# Sheet3.net
KiCad netlist of a schematic drawn in Altium Designer
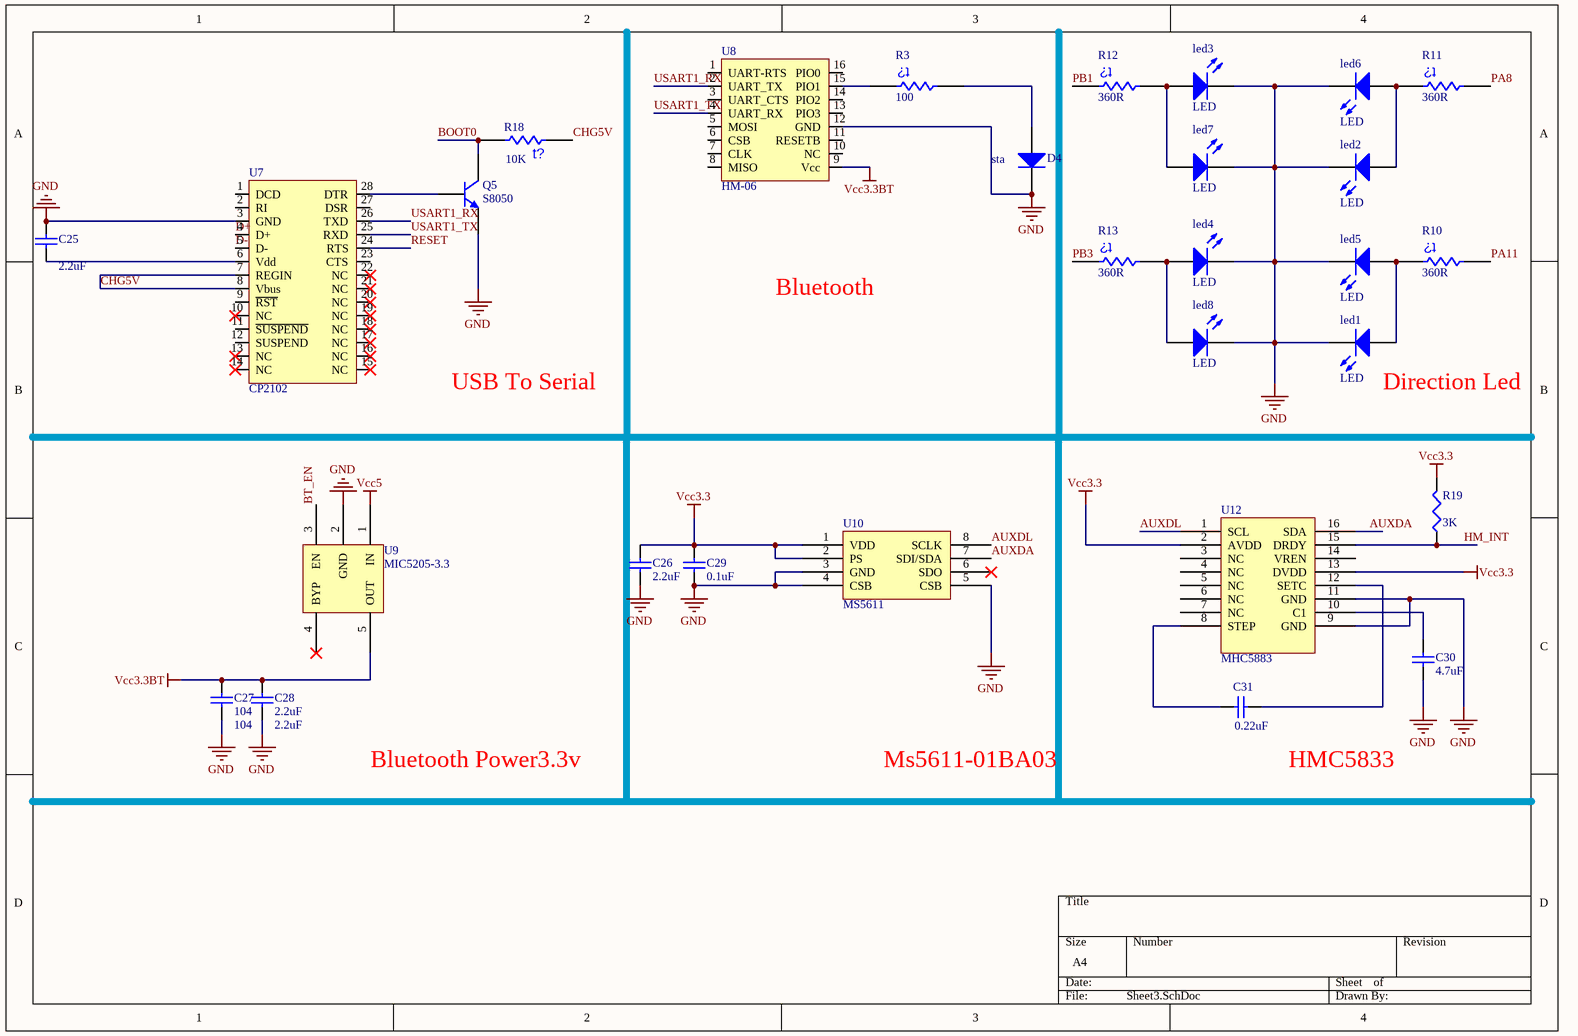
[diagram p0: Sheet3.SchDoc]

(export (version "E")
  (design (tool "Eeschema 10.0.6"))
  (components
    (comp (ref "C25")
      (value "2.2uF")
      (footprint "1608[0603]")
      (description "Capacitor (Semiconductor SIM Model)")
      (fields (field (name "PUBLISHER") "Altium Limited"))
      (libsource (lib "Miscellaneous Devices") (part "Cap Semi"))
    )
    (comp (ref "C26")
      (value "2.2uF")
      (footprint "1608[0603]")
      (description "Capacitor (Semiconductor SIM Model)")
      (fields (field (name "PUBLISHER") "Altium Limited"))
      (libsource (lib "Miscellaneous Devices") (part "Cap Semi"))
    )
    (comp (ref "C27")
      (value "104")
      (footprint "1608[0603]")
      (description "Capacitor (Semiconductor SIM Model)")
      (fields (field (name "ALTIUM_VALUE") "104") (field (name "PUBLISHER") "Altium Limited"))
      (libsource (lib "Miscellaneous Devices") (part "Cap Semi"))
    )
    (comp (ref "C28")
      (value "2.2uF")
      (footprint "1608[0603]")
      (description "Capacitor (Semiconductor SIM Model)")
      (fields (field (name "ALTIUM_VALUE") "2.2uF") (field (name "PUBLISHER") "Altium Limited"))
      (libsource (lib "Miscellaneous Devices") (part "Cap Semi"))
    )
    (comp (ref "C29")
      (value "0.1uF")
      (footprint "1608[0603]")
      (description "Capacitor (Semiconductor SIM Model)")
      (fields (field (name "PUBLISHER") "Altium Limited"))
      (libsource (lib "Miscellaneous Devices") (part "Cap Semi"))
    )
    (comp (ref "C30")
      (value "4.7uF")
      (footprint "1608[0603]")
      (description "Capacitor (Semiconductor SIM Model)")
      (fields (field (name "PUBLISHER") "Altium Limited"))
      (libsource (lib "Miscellaneous Devices") (part "Cap Semi"))
    )
    (comp (ref "C31")
      (value "0.22uF")
      (footprint "1608[0603]")
      (description "Capacitor (Semiconductor SIM Model)")
      (fields (field (name "PUBLISHER") "Altium Limited"))
      (libsource (lib "Miscellaneous Devices") (part "Cap Semi"))
    )
    (comp (ref "D4")
      (value "sta")
      (footprint "6-0805_N")
      (description "Default Diode")
      (fields (field (name "PUBLISHER") "Altium Limited"))
      (libsource (lib "Miscellaneous Devices") (part "Diode"))
    )
    (comp (ref "led1")
      (value "LED")
      (footprint "6-0805_N")
      (description "Typical RED, GREEN, YELLOW, AMBER GaAs LED")
      (fields (field (name "PUBLISHER") "Altium Limited"))
      (libsource (lib "Miscellaneous Devices") (part "LED2"))
    )
    (comp (ref "led2")
      (value "LED")
      (footprint "6-0805_N")
      (description "Typical RED, GREEN, YELLOW, AMBER GaAs LED")
      (fields (field (name "PUBLISHER") "Altium Limited"))
      (libsource (lib "Miscellaneous Devices") (part "LED2"))
    )
    (comp (ref "led3")
      (value "LED")
      (footprint "6-0805_N")
      (description "Typical RED, GREEN, YELLOW, AMBER GaAs LED")
      (fields (field (name "PUBLISHER") "Altium Limited"))
      (libsource (lib "Miscellaneous Devices") (part "LED2"))
    )
    (comp (ref "led4")
      (value "LED")
      (footprint "6-0805_N")
      (description "Typical RED, GREEN, YELLOW, AMBER GaAs LED")
      (fields (field (name "PUBLISHER") "Altium Limited"))
      (libsource (lib "Miscellaneous Devices") (part "LED2"))
    )
    (comp (ref "led5")
      (value "LED")
      (footprint "6-0805_N")
      (description "Typical RED, GREEN, YELLOW, AMBER GaAs LED")
      (fields (field (name "PUBLISHER") "Altium Limited"))
      (libsource (lib "Miscellaneous Devices") (part "LED2"))
    )
    (comp (ref "led6")
      (value "LED")
      (footprint "6-0805_N")
      (description "Typical RED, GREEN, YELLOW, AMBER GaAs LED")
      (fields (field (name "PUBLISHER") "Altium Limited"))
      (libsource (lib "Miscellaneous Devices") (part "LED2"))
    )
    (comp (ref "led7")
      (value "LED")
      (footprint "6-0805_N")
      (description "Typical RED, GREEN, YELLOW, AMBER GaAs LED")
      (fields (field (name "PUBLISHER") "Altium Limited"))
      (libsource (lib "Miscellaneous Devices") (part "LED2"))
    )
    (comp (ref "led8")
      (value "LED")
      (footprint "6-0805_N")
      (description "Typical RED, GREEN, YELLOW, AMBER GaAs LED")
      (fields (field (name "PUBLISHER") "Altium Limited"))
      (libsource (lib "Miscellaneous Devices") (part "LED2"))
    )
    (comp (ref "Q5")
      (value "S8050")
      (footprint "SOT-23B_N")
      (description "NPN Bipolar Transistor")
      (fields (field (name "PUBLISHER") "Altium Limited"))
      (libsource (lib "Miscellaneous Devices") (part "QNPN"))
    )
    (comp (ref "R3")
      (value "100")
      (footprint "6-0805_N")
      (fields (field (name "PUBLISHER") "Altium Limited"))
      (libsource (lib "Miscellaneous Devices") (part "Res Thermal"))
    )
    (comp (ref "R10")
      (value "360R")
      (footprint "6-0805_N")
      (fields (field (name "PUBLISHER") "Altium Limited"))
      (libsource (lib "Miscellaneous Devices") (part "Res Thermal"))
    )
    (comp (ref "R11")
      (value "360R")
      (footprint "6-0805_N")
      (fields (field (name "PUBLISHER") "Altium Limited"))
      (libsource (lib "Miscellaneous Devices") (part "Res Thermal"))
    )
    (comp (ref "R12")
      (value "360R")
      (footprint "6-0805_N")
      (fields (field (name "PUBLISHER") "Altium Limited"))
      (libsource (lib "Miscellaneous Devices") (part "Res Thermal"))
    )
    (comp (ref "R13")
      (value "360R")
      (footprint "6-0805_N")
      (fields (field (name "PUBLISHER") "Altium Limited"))
      (libsource (lib "Miscellaneous Devices") (part "Res Thermal"))
    )
    (comp (ref "R18")
      (value "10K")
      (footprint "6-0805_N")
      (fields (field (name "PUBLISHER") "Altium Limited"))
      (libsource (lib "Miscellaneous Devices") (part "Res Thermal"))
    )
    (comp (ref "R19")
      (value "3K")
      (footprint "0805")
      (description "Resistor")
      (fields (field (name "PUBLISHER") "Altium Limited"))
      (libsource (lib "Miscellaneous Devices") (part "Res3"))
    )
    (comp (ref "U7") (value "CP2102") (footprint "cp2102") (libsource (lib "stm32") (part "CP2102")))
    (comp (ref "U8") (value "HM-06") (footprint "HM-11") (libsource (lib "stm32") (part "bluetooth")))
    (comp (ref "U9")
      (value "MIC5205-3.3")
      (footprint "SOT95P280X120-5N")
      (libsource (lib "stm32") (part "MIC5205-3.3"))
    )
    (comp (ref "U10")
      (value "MS5611")
      (footprint "U6 - duplicate1")
      (libsource (lib "Ms5611") (part "Component_1"))
    )
    (comp (ref "U12")
      (value "HMC5833")
      (footprint "QFN50P302X302X90-16N")
      (libsource (lib "HMC5883") (part "Component_1"))
    )
  )
  (nets
    (net (code "1") (name "/AUXDA") (class "Default")
      (node (ref "U10") (pin "7") (pinfunction "SDI/SDA_7") (pintype "passive"))
      (node (ref "U12") (pin "16") (pinfunction "SDA_16") (pintype "passive"))
    )
    (net (code "2") (name "/AUXDL") (class "Default")
      (node (ref "U10") (pin "8") (pinfunction "SCLK_8") (pintype "passive"))
      (node (ref "U12") (pin "1") (pinfunction "SCL_1") (pintype "passive"))
    )
    (net (code "3") (name "/BOOT0") (class "Default")
      (node (ref "Q5") (pin "1") (pinfunction "C_1") (pintype "passive"))
      (node (ref "R18") (pin "2") (pinfunction "2_2") (pintype "passive"))
    )
    (net (code "4") (name "/BT_EN") (class "Default")
      (node (ref "U9") (pin "3") (pinfunction "EN_3") (pintype "passive"))
    )
    (net (code "7") (name "/CHG5V") (class "Default")
      (node (ref "R18") (pin "1") (pinfunction "1_1") (pintype "passive"))
      (node (ref "U7") (pin "7") (pinfunction "REGIN_7") (pintype "passive"))
      (node (ref "U7") (pin "8") (pinfunction "Vbus_8") (pintype "passive"))
    )
    (net (code "8") (name "/D+") (class "Default")
      (node (ref "U7") (pin "4") (pinfunction "D+_4") (pintype "passive"))
    )
    (net (code "9") (name "/D-") (class "Default")
      (node (ref "U7") (pin "5") (pinfunction "D-_5") (pintype "passive"))
    )
    (net (code "12") (name "/HM_INT") (class "Default")
      (node (ref "R19") (pin "1") (pinfunction "1_1") (pintype "passive"))
      (node (ref "U12") (pin "15") (pinfunction "DRDY_15") (pintype "passive"))
    )
    (net (code "14") (name "/PA8") (class "Default")
      (node (ref "R11") (pin "2") (pinfunction "2_2") (pintype "passive"))
    )
    (net (code "15") (name "/PA11") (class "Default")
      (node (ref "R10") (pin "2") (pinfunction "2_2") (pintype "passive"))
    )
    (net (code "16") (name "/PB1") (class "Default")
      (node (ref "R12") (pin "1") (pinfunction "1_1") (pintype "passive"))
    )
    (net (code "17") (name "/PB3") (class "Default")
      (node (ref "R13") (pin "1") (pinfunction "1_1") (pintype "passive"))
    )
    (net (code "18") (name "/RESET") (class "Default")
      (node (ref "U7") (pin "24") (pinfunction "RTS_24") (pintype "passive"))
    )
    (net (code "19") (name "/USART1_RX") (class "Default")
      (node (ref "U7") (pin "26") (pinfunction "TXD_26") (pintype "passive"))
      (node (ref "U8") (pin "2") (pinfunction "UART_TX_2") (pintype "passive"))
    )
    (net (code "20") (name "/USART1_TX") (class "Default")
      (node (ref "U7") (pin "25") (pinfunction "RXD_25") (pintype "passive"))
      (node (ref "U8") (pin "4") (pinfunction "UART_RX_4") (pintype "passive"))
    )
    (net (code "22") (name "GND") (class "Default")
      (node (ref "C25") (pin "1") (pinfunction "1_1") (pintype "passive"))
      (node (ref "C26") (pin "1") (pinfunction "1_1") (pintype "passive"))
      (node (ref "C27") (pin "2") (pinfunction "2_2") (pintype "passive"))
      (node (ref "C28") (pin "2") (pinfunction "2_2") (pintype "passive"))
      (node (ref "C29") (pin "1") (pinfunction "1_1") (pintype "passive"))
      (node (ref "C30") (pin "1") (pinfunction "1_1") (pintype "passive"))
      (node (ref "D4") (pin "2") (pinfunction "K_2") (pintype "passive"))
      (node (ref "Q5") (pin "3") (pinfunction "E_3") (pintype "passive"))
      (node (ref "U10") (pin "3") (pinfunction "GND_3") (pintype "passive"))
      (node (ref "U10") (pin "4") (pinfunction "CSB_4") (pintype "passive"))
      (node (ref "U10") (pin "5") (pinfunction "CSB_5") (pintype "passive"))
      (node (ref "U12") (pin "11") (pinfunction "GND_11") (pintype "passive"))
      (node (ref "U12") (pin "9") (pinfunction "GND_9") (pintype "passive"))
      (node (ref "U7") (pin "3") (pinfunction "GND_3") (pintype "passive"))
      (node (ref "U8") (pin "12") (pinfunction "GND_12") (pintype "passive"))
      (node (ref "U9") (pin "2") (pinfunction "GND_2") (pintype "passive"))
      (node (ref "led1") (pin "2") (pinfunction "K_2") (pintype "passive"))
      (node (ref "led2") (pin "2") (pinfunction "K_2") (pintype "passive"))
      (node (ref "led3") (pin "2") (pinfunction "K_2") (pintype "passive"))
      (node (ref "led4") (pin "2") (pinfunction "K_2") (pintype "passive"))
      (node (ref "led5") (pin "2") (pinfunction "K_2") (pintype "passive"))
      (node (ref "led6") (pin "2") (pinfunction "K_2") (pintype "passive"))
      (node (ref "led7") (pin "2") (pinfunction "K_2") (pintype "passive"))
      (node (ref "led8") (pin "2") (pinfunction "K_2") (pintype "passive"))
    )
    (net (code "23") (name "Net-(D4-A)") (class "Default")
      (node (ref "D4") (pin "1") (pinfunction "A_1") (pintype "passive"))
      (node (ref "R3") (pin "2") (pinfunction "2_2") (pintype "passive"))
    )
    (net (code "24") (name "Net-(Q5-B)") (class "Default")
      (node (ref "Q5") (pin "2") (pinfunction "B_2") (pintype "passive"))
      (node (ref "U7") (pin "28") (pinfunction "DTR_28") (pintype "passive"))
    )
    (net (code "25") (name "Net-(U7-Vdd)") (class "Default")
      (node (ref "C25") (pin "2") (pinfunction "2_2") (pintype "passive"))
      (node (ref "U7") (pin "6") (pinfunction "Vdd_6") (pintype "passive"))
    )
    (net (code "26") (name "Net-(U8-PIO1)") (class "Default")
      (node (ref "R3") (pin "1") (pinfunction "1_1") (pintype "passive"))
      (node (ref "U8") (pin "15") (pinfunction "PIO1_15") (pintype "passive"))
    )
    (net (code "27") (name "Net-(U12-C1)") (class "Default")
      (node (ref "C30") (pin "2") (pinfunction "2_2") (pintype "passive"))
      (node (ref "U12") (pin "10") (pinfunction "C1_10") (pintype "passive"))
    )
    (net (code "28") (name "Net-(U12-SETC)") (class "Default")
      (node (ref "C31") (pin "2") (pinfunction "2_2") (pintype "passive"))
      (node (ref "U12") (pin "12") (pinfunction "SETC_12") (pintype "passive"))
    )
    (net (code "29") (name "Net-(U12-STEP)") (class "Default")
      (node (ref "C31") (pin "1") (pinfunction "1_1") (pintype "passive"))
      (node (ref "U12") (pin "8") (pinfunction "STEP_8") (pintype "passive"))
    )
    (net (code "30") (name "Net-(led1-A)") (class "Default")
      (node (ref "R10") (pin "1") (pinfunction "1_1") (pintype "passive"))
      (node (ref "led1") (pin "1") (pinfunction "A_1") (pintype "passive"))
      (node (ref "led5") (pin "1") (pinfunction "A_1") (pintype "passive"))
    )
    (net (code "31") (name "Net-(led2-A)") (class "Default")
      (node (ref "R11") (pin "1") (pinfunction "1_1") (pintype "passive"))
      (node (ref "led2") (pin "1") (pinfunction "A_1") (pintype "passive"))
      (node (ref "led6") (pin "1") (pinfunction "A_1") (pintype "passive"))
    )
    (net (code "32") (name "Net-(led3-A)") (class "Default")
      (node (ref "R12") (pin "2") (pinfunction "2_2") (pintype "passive"))
      (node (ref "led3") (pin "1") (pinfunction "A_1") (pintype "passive"))
      (node (ref "led7") (pin "1") (pinfunction "A_1") (pintype "passive"))
    )
    (net (code "33") (name "Net-(led4-A)") (class "Default")
      (node (ref "R13") (pin "2") (pinfunction "2_2") (pintype "passive"))
      (node (ref "led4") (pin "1") (pinfunction "A_1") (pintype "passive"))
      (node (ref "led8") (pin "1") (pinfunction "A_1") (pintype "passive"))
    )
    (net (code "34") (name "Vcc3.3") (class "Default")
      (node (ref "C26") (pin "2") (pinfunction "2_2") (pintype "passive"))
      (node (ref "C29") (pin "2") (pinfunction "2_2") (pintype "passive"))
      (node (ref "R19") (pin "2") (pinfunction "2_2") (pintype "passive"))
      (node (ref "U10") (pin "1") (pinfunction "VDD_1") (pintype "passive"))
      (node (ref "U10") (pin "2") (pinfunction "PS_2") (pintype "passive"))
      (node (ref "U12") (pin "13") (pinfunction "DVDD_13") (pintype "passive"))
      (node (ref "U12") (pin "2") (pinfunction "AVDD_2") (pintype "passive"))
    )
    (net (code "35") (name "Vcc3.3BT") (class "Default")
      (node (ref "C27") (pin "1") (pinfunction "1_1") (pintype "passive"))
      (node (ref "C28") (pin "1") (pinfunction "1_1") (pintype "passive"))
      (node (ref "U8") (pin "9") (pinfunction "Vcc_9") (pintype "passive"))
      (node (ref "U9") (pin "5") (pinfunction "OUT_5") (pintype "passive"))
    )
    (net (code "36") (name "Vcc5") (class "Default")
      (node (ref "U9") (pin "1") (pinfunction "IN_1") (pintype "passive"))
    )
    (net (code "37") (name "unconnected-(U7-CTS-Pad23)") (class "Default")
      (node (ref "U7") (pin "23") (pinfunction "CTS_23") (pintype "passive"))
    )
    (net (code "38") (name "unconnected-(U7-DCD-Pad1)") (class "Default")
      (node (ref "U7") (pin "1") (pinfunction "DCD_1") (pintype "passive"))
    )
    (net (code "39") (name "unconnected-(U7-DSR-Pad27)") (class "Default")
      (node (ref "U7") (pin "27") (pinfunction "DSR_27") (pintype "passive"))
    )
    (net (code "40") (name "unconnected-(U7-NC-Pad10)") (class "Default")
      (node (ref "U7") (pin "10") (pinfunction "NC_10") (pintype "passive+no_connect"))
    )
    (net (code "41") (name "unconnected-(U7-NC-Pad13)") (class "Default")
      (node (ref "U7") (pin "13") (pinfunction "NC_13") (pintype "passive+no_connect"))
    )
    (net (code "42") (name "unconnected-(U7-NC-Pad14)") (class "Default")
      (node (ref "U7") (pin "14") (pinfunction "NC_14") (pintype "passive+no_connect"))
    )
    (net (code "43") (name "unconnected-(U7-NC-Pad15)") (class "Default")
      (node (ref "U7") (pin "15") (pinfunction "NC_15") (pintype "passive+no_connect"))
    )
    (net (code "44") (name "unconnected-(U7-NC-Pad16)") (class "Default")
      (node (ref "U7") (pin "16") (pinfunction "NC_16") (pintype "passive+no_connect"))
    )
    (net (code "45") (name "unconnected-(U7-NC-Pad17)") (class "Default")
      (node (ref "U7") (pin "17") (pinfunction "NC_17") (pintype "passive+no_connect"))
    )
    (net (code "46") (name "unconnected-(U7-NC-Pad18)") (class "Default")
      (node (ref "U7") (pin "18") (pinfunction "NC_18") (pintype "passive+no_connect"))
    )
    (net (code "47") (name "unconnected-(U7-NC-Pad19)") (class "Default")
      (node (ref "U7") (pin "19") (pinfunction "NC_19") (pintype "passive+no_connect"))
    )
    (net (code "48") (name "unconnected-(U7-NC-Pad20)") (class "Default")
      (node (ref "U7") (pin "20") (pinfunction "NC_20") (pintype "passive+no_connect"))
    )
    (net (code "49") (name "unconnected-(U7-NC-Pad21)") (class "Default")
      (node (ref "U7") (pin "21") (pinfunction "NC_21") (pintype "passive+no_connect"))
    )
    (net (code "50") (name "unconnected-(U7-NC-Pad22)") (class "Default")
      (node (ref "U7") (pin "22") (pinfunction "NC_22") (pintype "passive+no_connect"))
    )
    (net (code "51") (name "unconnected-(U7-RI-Pad2)") (class "Default")
      (node (ref "U7") (pin "2") (pinfunction "RI_2") (pintype "passive"))
    )
    (net (code "52") (name "unconnected-(U7-SUSPEND-Pad12)") (class "Default")
      (node (ref "U7") (pin "12") (pinfunction "SUSPEND_12") (pintype "passive"))
    )
    (net (code "53") (name "unconnected-(U7-~{RST}-Pad9)") (class "Default")
      (node (ref "U7") (pin "9") (pinfunction "~{RST}_9") (pintype "passive"))
    )
    (net (code "54") (name "unconnected-(U7-~{SUSPEND}-Pad11)") (class "Default")
      (node (ref "U7") (pin "11") (pinfunction "~{SUSPEND}_11") (pintype "passive"))
    )
    (net (code "55") (name "unconnected-(U8-CLK-Pad7)") (class "Default")
      (node (ref "U8") (pin "7") (pinfunction "CLK_7") (pintype "passive"))
    )
    (net (code "56") (name "unconnected-(U8-CSB-Pad6)") (class "Default")
      (node (ref "U8") (pin "6") (pinfunction "CSB_6") (pintype "passive"))
    )
    (net (code "57") (name "unconnected-(U8-MISO-Pad8)") (class "Default")
      (node (ref "U8") (pin "8") (pinfunction "MISO_8") (pintype "passive"))
    )
    (net (code "58") (name "unconnected-(U8-MOSI-Pad5)") (class "Default")
      (node (ref "U8") (pin "5") (pinfunction "MOSI_5") (pintype "passive"))
    )
    (net (code "59") (name "unconnected-(U8-NC-Pad10)") (class "Default")
      (node (ref "U8") (pin "10") (pinfunction "NC_10") (pintype "passive"))
    )
    (net (code "60") (name "unconnected-(U8-PIO0-Pad16)") (class "Default")
      (node (ref "U8") (pin "16") (pinfunction "PIO0_16") (pintype "passive"))
    )
    (net (code "61") (name "unconnected-(U8-PIO2-Pad14)") (class "Default")
      (node (ref "U8") (pin "14") (pinfunction "PIO2_14") (pintype "passive"))
    )
    (net (code "62") (name "unconnected-(U8-PIO3-Pad13)") (class "Default")
      (node (ref "U8") (pin "13") (pinfunction "PIO3_13") (pintype "passive"))
    )
    (net (code "63") (name "unconnected-(U8-RESETB-Pad11)") (class "Default")
      (node (ref "U8") (pin "11") (pinfunction "RESETB_11") (pintype "passive"))
    )
    (net (code "64") (name "unconnected-(U8-UART-RTS-Pad1)") (class "Default")
      (node (ref "U8") (pin "1") (pinfunction "UART-RTS_1") (pintype "passive"))
    )
    (net (code "65") (name "unconnected-(U8-UART_CTS-Pad3)") (class "Default")
      (node (ref "U8") (pin "3") (pinfunction "UART_CTS_3") (pintype "passive"))
    )
    (net (code "66") (name "unconnected-(U9-BYP-Pad4)") (class "Default")
      (node (ref "U9") (pin "4") (pinfunction "BYP_4") (pintype "passive+no_connect"))
    )
    (net (code "67") (name "unconnected-(U10-SDO-Pad6)") (class "Default")
      (node (ref "U10") (pin "6") (pinfunction "SDO_6") (pintype "passive+no_connect"))
    )
    (net (code "68") (name "unconnected-(U12-NC-Pad3)") (class "Default")
      (node (ref "U12") (pin "3") (pinfunction "NC_3") (pintype "passive"))
    )
    (net (code "69") (name "unconnected-(U12-NC-Pad4)") (class "Default")
      (node (ref "U12") (pin "4") (pinfunction "NC_4") (pintype "passive"))
    )
    (net (code "70") (name "unconnected-(U12-NC-Pad5)") (class "Default")
      (node (ref "U12") (pin "5") (pinfunction "NC_5") (pintype "passive"))
    )
    (net (code "71") (name "unconnected-(U12-NC-Pad6)") (class "Default")
      (node (ref "U12") (pin "6") (pinfunction "NC_6") (pintype "passive"))
    )
    (net (code "72") (name "unconnected-(U12-NC-Pad7)") (class "Default")
      (node (ref "U12") (pin "7") (pinfunction "NC_7") (pintype "passive"))
    )
    (net (code "73") (name "unconnected-(U12-VREN-Pad14)") (class "Default")
      (node (ref "U12") (pin "14") (pinfunction "VREN_14") (pintype "passive"))
    )
  )
)
